# rf_trsw.net
KiCad netlist of a schematic drawn in Altium Designer
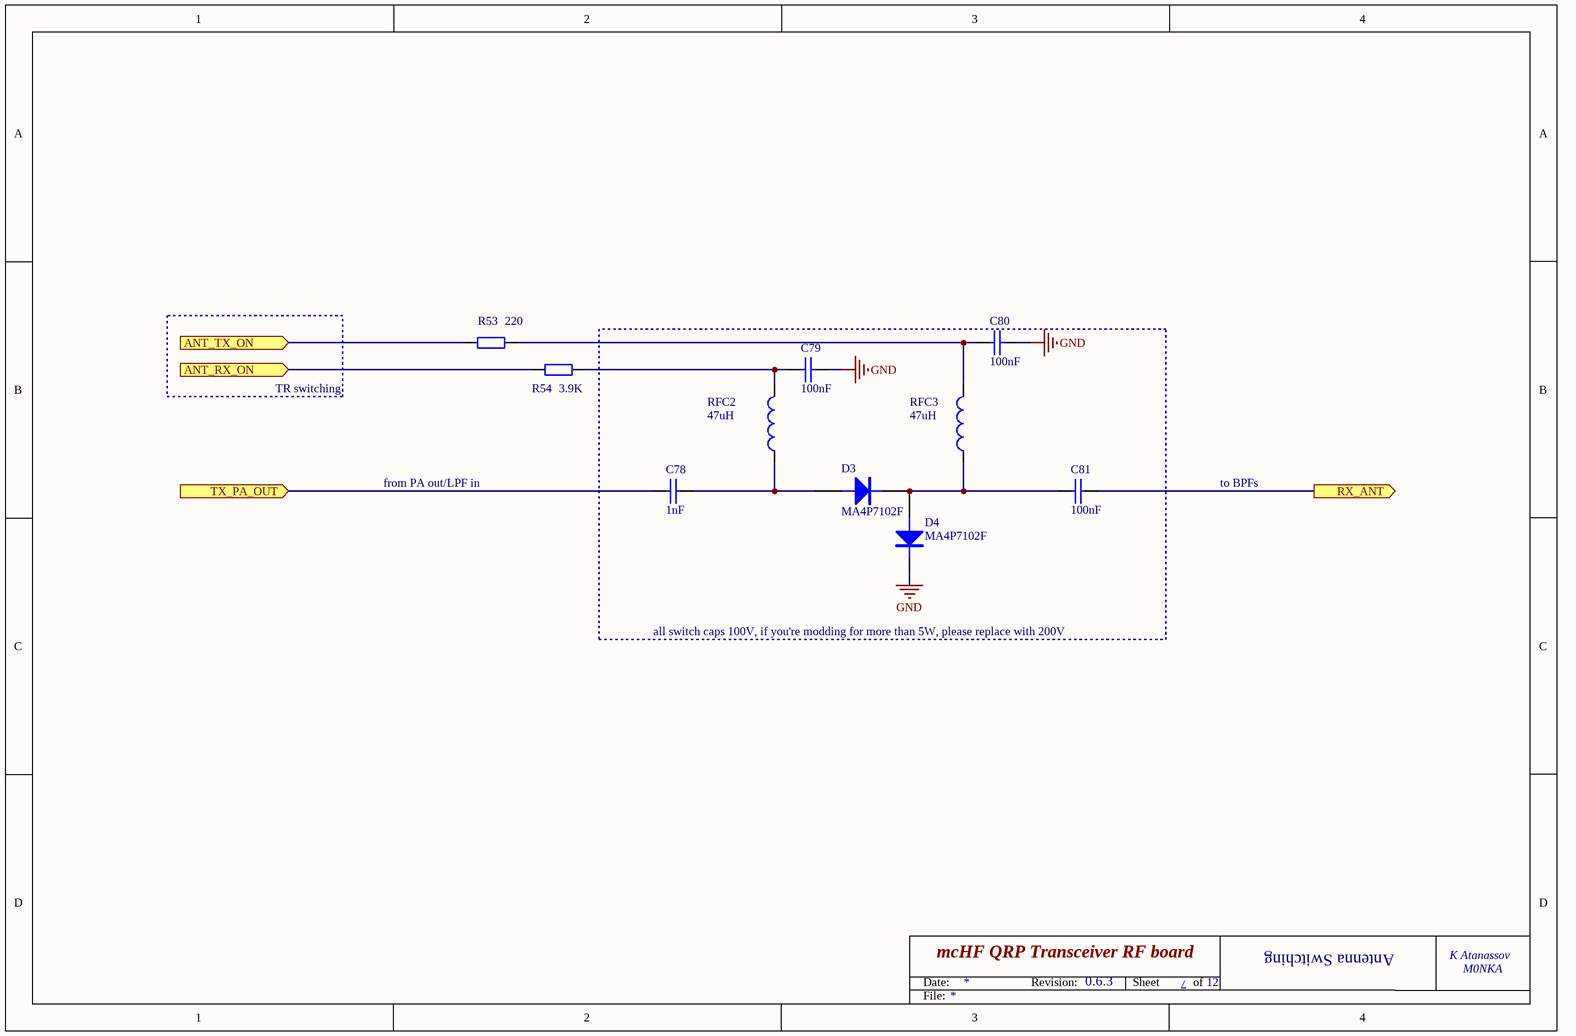
[diagram p0: rf_trsw.SchDoc]

(export (version "E")
  (design (tool "Eeschema 10.0.6"))
  (components
    (comp (ref "C78")
      (value "1nF")
      (footprint "0805-Pro")
      (description "Capacitor")
      (fields (field (name "VOLTAGE") "100V"))
      (libsource (lib "mcHF_rf") (part "CAP"))
    )
    (comp (ref "C79")
      (value "100nF")
      (footprint "0805-Pro")
      (description "Capacitor")
      (fields (field (name "VOLTAGE") "100V"))
      (libsource (lib "mcHF_rf") (part "CAP"))
    )
    (comp (ref "C80")
      (value "100nF")
      (footprint "0805-Pro")
      (description "Capacitor")
      (fields (field (name "VOLTAGE") "100V"))
      (libsource (lib "mcHF_rf") (part "CAP"))
    )
    (comp (ref "C81")
      (value "100nF")
      (footprint "0805-Pro")
      (description "Capacitor")
      (fields (field (name "VOLTAGE") "100V"))
      (libsource (lib "mcHF_rf") (part "CAP"))
    )
    (comp (ref "D3")
      (value "MA4P7102F")
      (footprint "1072T")
      (description "MELF & HIPAX PIN Diod")
      (libsource (lib "mcHF_rf") (part "MA4P7102F"))
    )
    (comp (ref "D4")
      (value "MA4P7102F")
      (footprint "1072T")
      (description "MELF & HIPAX PIN Diod")
      (libsource (lib "mcHF_rf") (part "MA4P7102F"))
    )
    (comp (ref "R53")
      (value "220")
      (footprint "0805-Pro")
      (description "Resistor")
      (libsource (lib "mcHF_rf") (part "RES"))
    )
    (comp (ref "R54")
      (value "3.9K")
      (footprint "0805-Pro")
      (description "Resistor")
      (libsource (lib "") (part "RES_1"))
    )
    (comp (ref "RFC2")
      (value "47uH")
      (footprint "0805-Pro")
      (description "INDUCTOR, SIGNAL LINE, 4.7UH, 1005")
      (libsource (lib "mcHF_rf") (part "TDK-NLV25T"))
    )
    (comp (ref "RFC3")
      (value "47uH")
      (footprint "0805-Pro")
      (description "INDUCTOR, SIGNAL LINE, 4.7UH, 1005")
      (libsource (lib "mcHF_rf") (part "TDK-NLV25T"))
    )
  )
  (nets
    (net (code "1") (name "/ANT_RX_ON") (class "Default")
      (node (ref "R54") (pin "1") (pinfunction "1_1") (pintype "passive"))
    )
    (net (code "2") (name "/ANT_TX_ON") (class "Default")
      (node (ref "R53") (pin "2") (pinfunction "2_2") (pintype "passive"))
    )
    (net (code "3") (name "/RX_ANT") (class "Default")
      (node (ref "C81") (pin "1") (pinfunction "1_1") (pintype "passive"))
    )
    (net (code "4") (name "/TX_PA_OUT") (class "Default")
      (node (ref "C78") (pin "2") (pinfunction "2_2") (pintype "passive"))
    )
    (net (code "5") (name "GND") (class "Default")
      (node (ref "C79") (pin "1") (pinfunction "1_1") (pintype "passive"))
      (node (ref "C80") (pin "1") (pinfunction "1_1") (pintype "passive"))
      (node (ref "D4") (pin "1") (pinfunction "K_1") (pintype "passive"))
    )
    (net (code "6") (name "Net-(C79-Pad2)") (class "Default")
      (node (ref "C79") (pin "2") (pinfunction "2_2") (pintype "passive"))
      (node (ref "R54") (pin "2") (pinfunction "2_2") (pintype "passive"))
      (node (ref "RFC2") (pin "2") (pinfunction "2_2") (pintype "passive"))
    )
    (net (code "7") (name "Net-(C80-Pad2)") (class "Default")
      (node (ref "C80") (pin "2") (pinfunction "2_2") (pintype "passive"))
      (node (ref "R53") (pin "1") (pinfunction "1_1") (pintype "passive"))
      (node (ref "RFC3") (pin "2") (pinfunction "2_2") (pintype "passive"))
    )
    (net (code "8") (name "Net-(D3-A)") (class "Default")
      (node (ref "C78") (pin "1") (pinfunction "1_1") (pintype "passive"))
      (node (ref "D3") (pin "2") (pinfunction "A_2") (pintype "passive"))
      (node (ref "RFC2") (pin "1") (pinfunction "1_1") (pintype "passive"))
    )
    (net (code "9") (name "Net-(D3-K)") (class "Default")
      (node (ref "C81") (pin "2") (pinfunction "2_2") (pintype "passive"))
      (node (ref "D3") (pin "1") (pinfunction "K_1") (pintype "passive"))
      (node (ref "D4") (pin "2") (pinfunction "A_2") (pintype "passive"))
      (node (ref "RFC3") (pin "1") (pinfunction "1_1") (pintype "passive"))
    )
  )
)
